# 06_-_CPU_-_HDMI_LVDS.net
KiCad netlist of a schematic drawn in Altium Designer
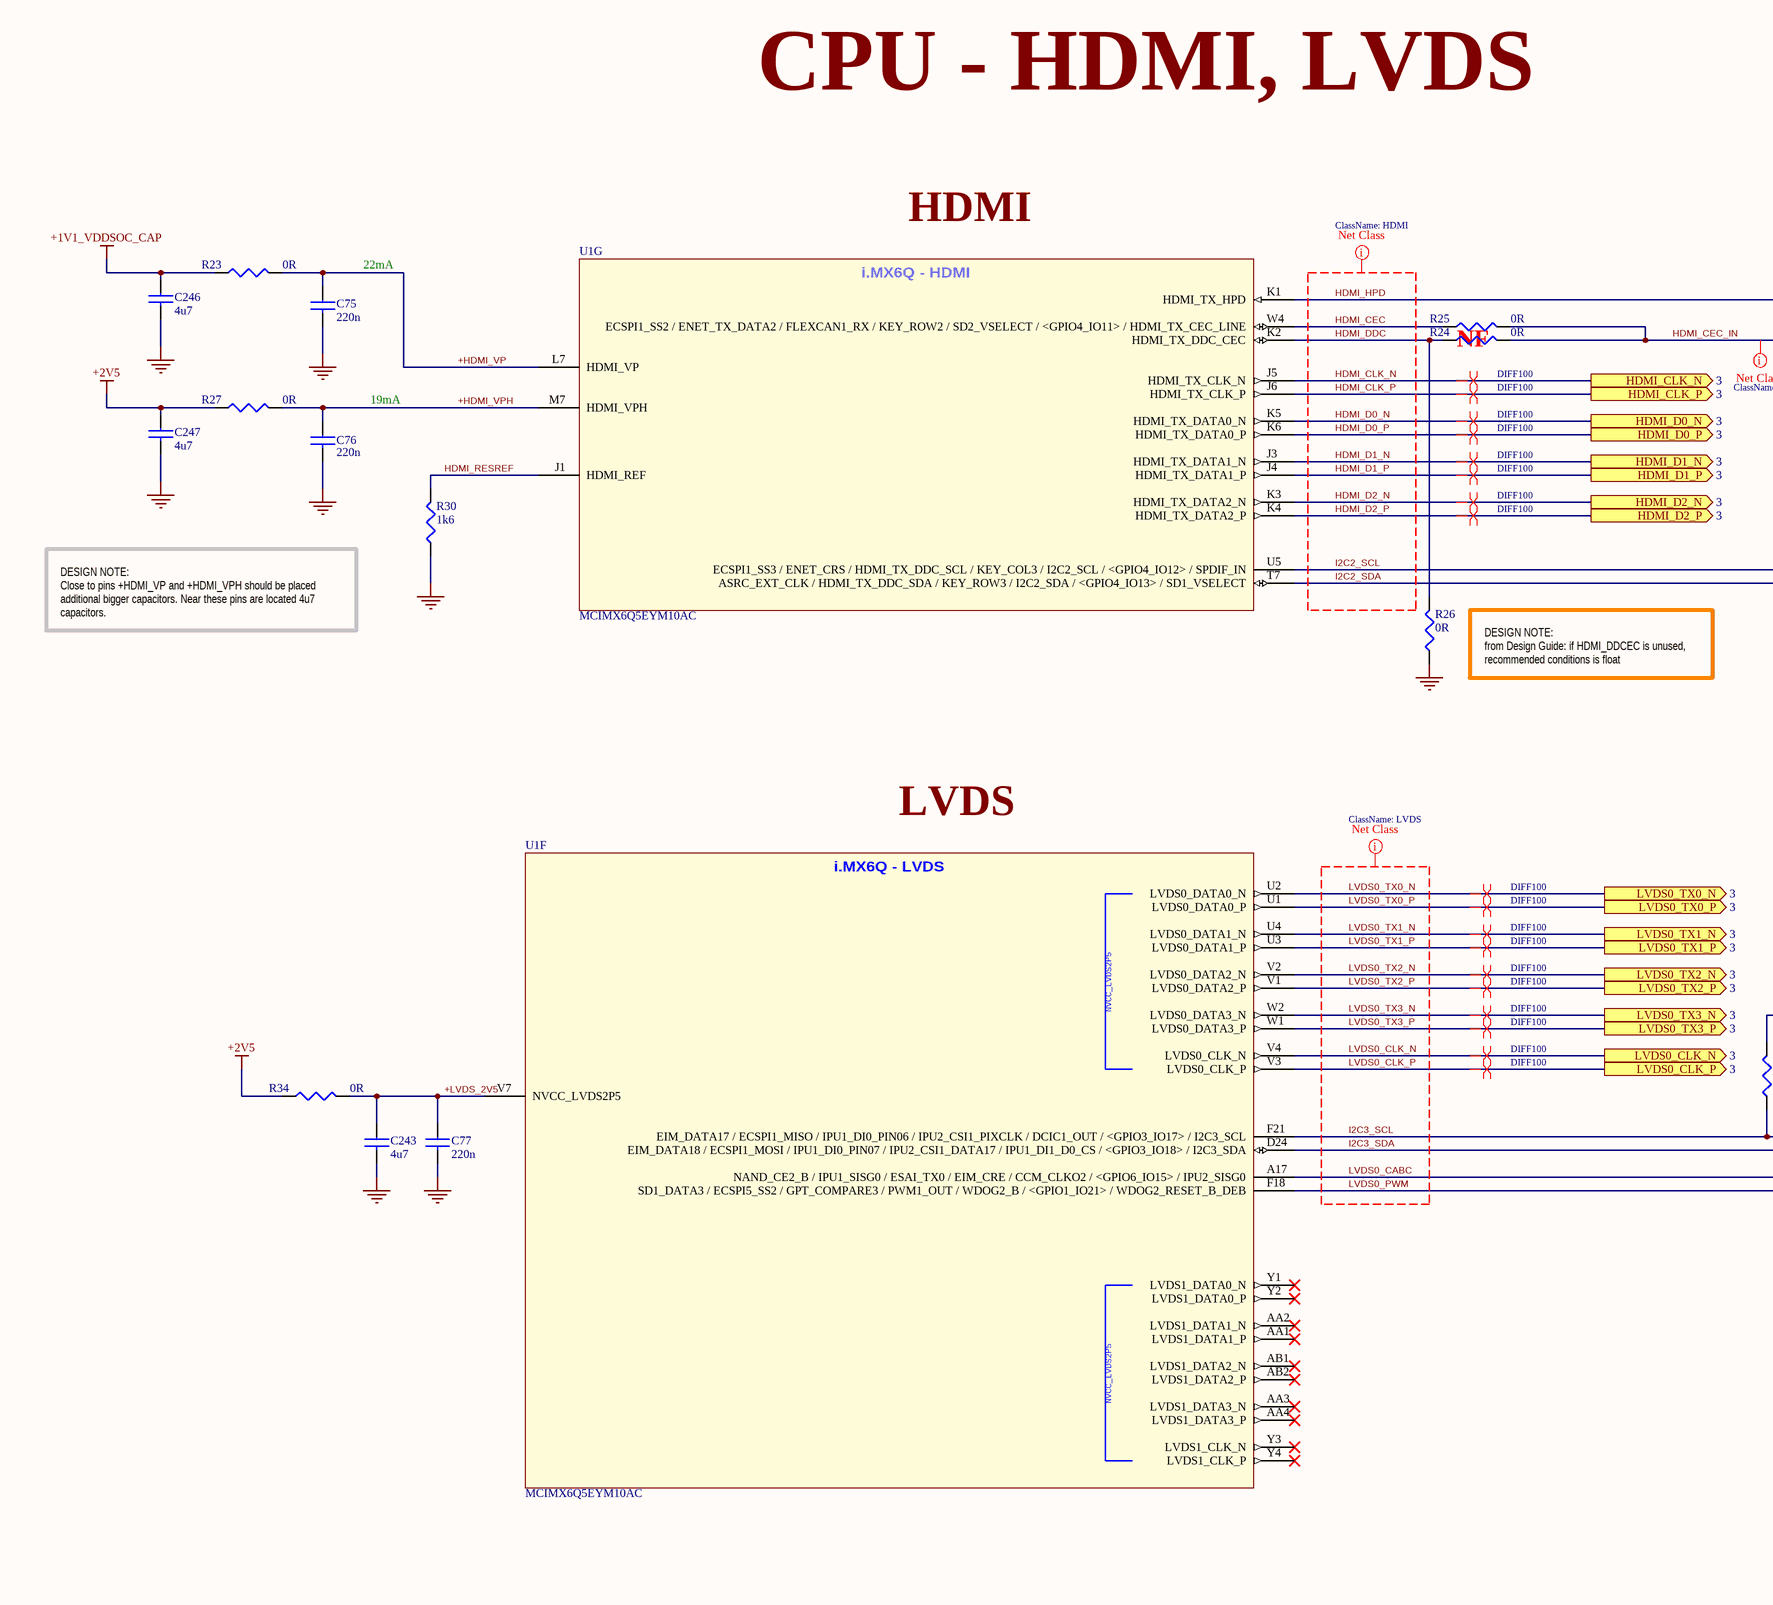
[diagram p0: [06] - CPU - HDMI, LVDS.SchDoc, left]
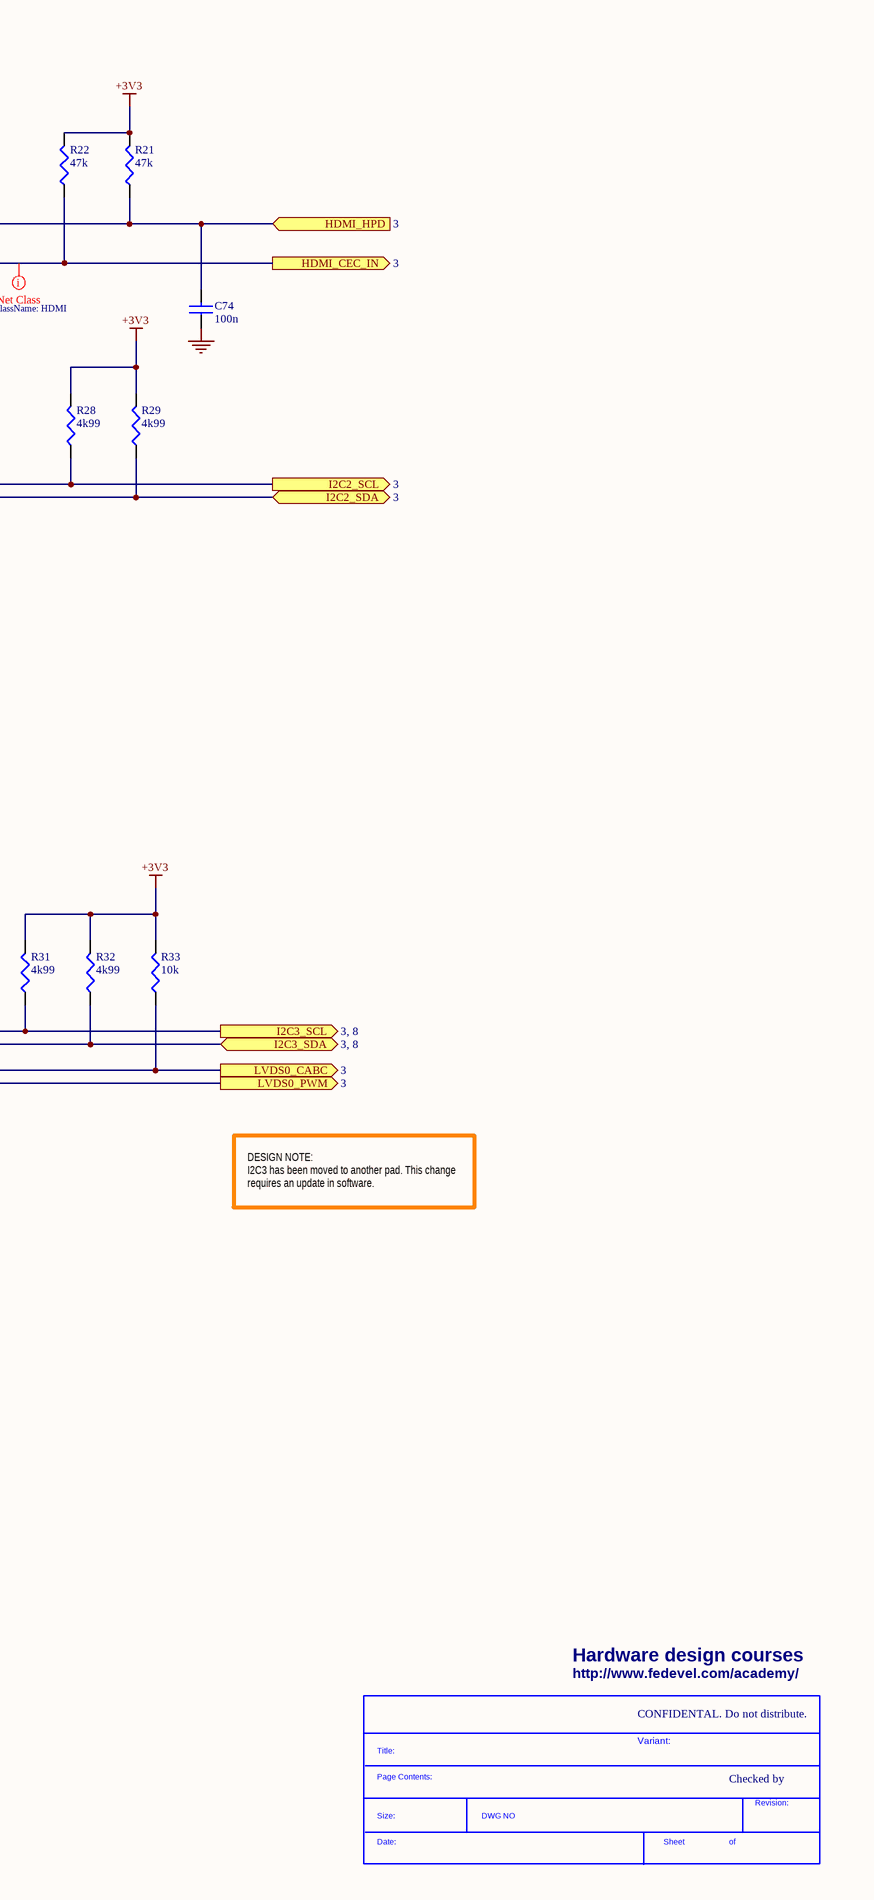
[diagram p1: [06] - CPU - HDMI, LVDS.SchDoc, right]

(export (version "E")
  (design (tool "Eeschema 10.0.6"))
  (components
    (comp (ref "C74")
      (value "100n")
      (footprint "C0402")
      (description "CAP CER .10UF 50V X5R 10% 0402")
      (fields
        (field (name "MANUFACTURER") "TDK Corporation")
        (field (name "MANUFACTURER PART NUMBER") "C1005X5R1H104K")
      )
      (libsource (lib "iMX6 Rex_V1I1") (part "C1005X5R1H104K"))
    )
    (comp (ref "C75")
      (value "220n")
      (footprint "C0402")
      (description "CAP CER .22UF 25V X5R 20% 0402")
      (fields
        (field (name "MANUFACTURER") "TDK Corporation")
        (field (name "MANUFACTURER PART NUMBER") "C1005X5R1E224M")
      )
      (libsource (lib "iMX6 Rex_V1I1") (part "C1005X5R1E224M"))
    )
    (comp (ref "C76")
      (value "220n")
      (footprint "C0402")
      (description "CAP CER .22UF 25V X5R 20% 0402")
      (fields
        (field (name "MANUFACTURER") "TDK Corporation")
        (field (name "MANUFACTURER PART NUMBER") "C1005X5R1E224M")
      )
      (libsource (lib "iMX6 Rex_V1I1") (part "C1005X5R1E224M"))
    )
    (comp (ref "C77")
      (value "220n")
      (footprint "C0402")
      (description "CAP CER .22UF 25V X5R 20% 0402")
      (fields
        (field (name "MANUFACTURER") "TDK Corporation")
        (field (name "MANUFACTURER PART NUMBER") "C1005X5R1E224M")
      )
      (libsource (lib "iMX6 Rex_V1I1") (part "C1005X5R1E224M"))
    )
    (comp (ref "C243")
      (value "4u7")
      (footprint "C0402")
      (description "CAP CER 4.7UF 10V 20% X5R 0402")
      (fields
        (field (name "MANUFACTURER") "TDK Corporation")
        (field (name "MANUFACTURER PART NUMBER") "C1005X5R1A475M")
        (field (name ".CHECKED PCB") "RF")
        (field (name ".CHECKED SCH") "RF")
      )
      (libsource (lib "iMX6 Rex_V1I1") (part "C1005X5R1A475M"))
    )
    (comp (ref "C246")
      (value "4u7")
      (footprint "C0402")
      (description "CAP CER 4.7UF 10V 20% X5R 0402")
      (fields
        (field (name "MANUFACTURER") "TDK Corporation")
        (field (name "MANUFACTURER PART NUMBER") "C1005X5R1A475M")
        (field (name ".CHECKED PCB") "RF")
        (field (name ".CHECKED SCH") "RF")
      )
      (libsource (lib "iMX6 Rex_V1I1") (part "C1005X5R1A475M"))
    )
    (comp (ref "C247")
      (value "4u7")
      (footprint "C0402")
      (description "CAP CER 4.7UF 10V 20% X5R 0402")
      (fields
        (field (name "MANUFACTURER") "TDK Corporation")
        (field (name "MANUFACTURER PART NUMBER") "C1005X5R1A475M")
        (field (name ".CHECKED PCB") "RF")
        (field (name ".CHECKED SCH") "RF")
      )
      (libsource (lib "iMX6 Rex_V1I1") (part "C1005X5R1A475M"))
    )
    (comp (ref "R21")
      (value "47k")
      (footprint "R0402")
      (description "RES 47.0K OHM 1/16W 1% 0402 SMD")
      (fields
        (field (name "MANUFACTURER") "Yageo")
        (field (name "MANUFACTURER PART NUMBER") "RC0402FR-0747KL")
      )
      (libsource (lib "iMX6 Rex_V1I1") (part "RC0402FR-0747KL"))
    )
    (comp (ref "R22")
      (value "47k")
      (footprint "R0402")
      (description "RES 47.0K OHM 1/16W 1% 0402 SMD")
      (fields
        (field (name "MANUFACTURER") "Yageo")
        (field (name "MANUFACTURER PART NUMBER") "RC0402FR-0747KL")
      )
      (libsource (lib "iMX6 Rex_V1I1") (part "RC0402FR-0747KL"))
    )
    (comp (ref "R23")
      (value "0R")
      (footprint "R0402")
      (description "RES 0.0 OHM 1/16W 0402 SMD")
      (fields
        (field (name "MANUFACTURER") "Yageo")
        (field (name "MANUFACTURER PART NUMBER") "RC0402JR-070RL")
      )
      (libsource (lib "iMX6 Rex_V1I1") (part "RC0402JR-070RL"))
    )
    (comp (ref "R24")
      (value "0R")
      (footprint "R0402")
      (description "RES 0.0 OHM 1/16W 0402 SMD")
      (fields
        (field (name "MANUFACTURER") "Yageo")
        (field (name "MANUFACTURER PART NUMBER") "RC0402JR-070RL")
      )
      (libsource (lib "iMX6 Rex_V1I1") (part "RC0402JR-070RL"))
    )
    (comp (ref "R25")
      (value "0R")
      (footprint "R0402")
      (description "RES 0.0 OHM 1/16W 0402 SMD")
      (fields
        (field (name "MANUFACTURER") "Yageo")
        (field (name "MANUFACTURER PART NUMBER") "RC0402JR-070RL")
      )
      (libsource (lib "iMX6 Rex_V1I1") (part "RC0402JR-070RL"))
    )
    (comp (ref "R26")
      (value "0R")
      (footprint "R0402")
      (description "RES 0.0 OHM 1/16W 0402 SMD")
      (fields
        (field (name "MANUFACTURER") "Yageo")
        (field (name "MANUFACTURER PART NUMBER") "RC0402JR-070RL")
      )
      (libsource (lib "iMX6 Rex_V1I1") (part "RC0402JR-070RL"))
    )
    (comp (ref "R27")
      (value "0R")
      (footprint "R0402")
      (description "RES 0.0 OHM 1/16W 0402 SMD")
      (fields
        (field (name "MANUFACTURER") "Yageo")
        (field (name "MANUFACTURER PART NUMBER") "RC0402JR-070RL")
      )
      (libsource (lib "iMX6 Rex_V1I1") (part "RC0402JR-070RL"))
    )
    (comp (ref "R28")
      (value "4k99")
      (footprint "R0402")
      (description "RES TF 4.99K OHM 1% 1/16W 0402")
      (fields
        (field (name "MANUFACTURER") "Stackpole Electronics Inc")
        (field (name "MANUFACTURER PART NUMBER") "RMCF0402FT4K99")
      )
      (libsource (lib "iMX6 Rex_V1I1") (part "RMCF0402FT4K99"))
    )
    (comp (ref "R29")
      (value "4k99")
      (footprint "R0402")
      (description "RES TF 4.99K OHM 1% 1/16W 0402")
      (fields
        (field (name "MANUFACTURER") "Stackpole Electronics Inc")
        (field (name "MANUFACTURER PART NUMBER") "RMCF0402FT4K99")
      )
      (libsource (lib "iMX6 Rex_V1I1") (part "RMCF0402FT4K99"))
    )
    (comp (ref "R30")
      (value "1k6")
      (footprint "R0402")
      (description "RES 1.6K OHM 1/10W 1% 0402 SMD")
      (fields
        (field (name "MANUFACTURER") "Panasonic Electronic Components")
        (field (name "MANUFACTURER PART NUMBER") "ERJ-2RKF1601X")
        (field (name ".CREATOR") "MM")
        (field (name ".CHECKED PCB") "RF, used by MM")
        (field (name ".CHECKED SCH") "MM, checked by RF")
      )
      (libsource (lib "iMX6 Rex_V1I1") (part "ERJ-2RKF1601X"))
    )
    (comp (ref "R31")
      (value "4k99")
      (footprint "R0402")
      (description "RES TF 4.99K OHM 1% 1/16W 0402")
      (fields
        (field (name "MANUFACTURER") "Stackpole Electronics Inc")
        (field (name "MANUFACTURER PART NUMBER") "RMCF0402FT4K99")
      )
      (libsource (lib "iMX6 Rex_V1I1") (part "RMCF0402FT4K99"))
    )
    (comp (ref "R32")
      (value "4k99")
      (footprint "R0402")
      (description "RES TF 4.99K OHM 1% 1/16W 0402")
      (fields
        (field (name "MANUFACTURER") "Stackpole Electronics Inc")
        (field (name "MANUFACTURER PART NUMBER") "RMCF0402FT4K99")
      )
      (libsource (lib "iMX6 Rex_V1I1") (part "RMCF0402FT4K99"))
    )
    (comp (ref "R33")
      (value "10k")
      (footprint "R0402")
      (description "RES 10.0K OHM 1/16W 1% 0402 SMD")
      (fields
        (field (name "MANUFACTURER") "Yageo")
        (field (name "MANUFACTURER PART NUMBER") "RC0402FR-0710KL")
      )
      (libsource (lib "iMX6 Rex_V1I1") (part "RC0402FR-0710KL"))
    )
    (comp (ref "R34")
      (value "0R")
      (footprint "R0402")
      (description "RES 0.0 OHM 1/16W 0402 SMD")
      (fields
        (field (name "MANUFACTURER") "Yageo")
        (field (name "MANUFACTURER PART NUMBER") "RC0402JR-070RL")
      )
      (libsource (lib "iMX6 Rex_V1I1") (part "RC0402JR-070RL"))
    )
    (comp (ref "U1")
      (value "MCIMX6Q5EYM10AC")
      (footprint "PBGA624")
      (description "IC MCU 32BIT ARM QUAD 624FCBGA")
      (fields
        (field (name "MANUFACTURER") "Freescale Semiconductor")
        (field (name ".CREATOR") "MM")
        (field (name ".CHECKED PCB") "MM, checked by RF")
        (field (name ".CHECKED SCH") "MM")
      )
      (libsource (lib "iMX6 Rex_V1I1") (part "MCIMX6Q5EYM10AC"))
    )
  )
  (nets
    (net (code "1") (name "+1V1_VDDSOC_CAP") (class "Default")
      (node (ref "C246") (pin "1") (pinfunction "1_1") (pintype "passive"))
      (node (ref "R23") (pin "1") (pinfunction "1_1") (pintype "passive"))
    )
    (net (code "2") (name "+2V5") (class "Default")
      (node (ref "C247") (pin "1") (pinfunction "1_1") (pintype "passive"))
      (node (ref "R27") (pin "1") (pinfunction "1_1") (pintype "passive"))
      (node (ref "R34") (pin "1") (pinfunction "1_1") (pintype "passive"))
    )
    (net (code "3") (name "+3V3") (class "Default")
      (node (ref "R21") (pin "2") (pinfunction "2_2") (pintype "passive"))
      (node (ref "R22") (pin "2") (pinfunction "2_2") (pintype "passive"))
      (node (ref "R28") (pin "2") (pinfunction "2_2") (pintype "passive"))
      (node (ref "R29") (pin "2") (pinfunction "2_2") (pintype "passive"))
      (node (ref "R31") (pin "2") (pinfunction "2_2") (pintype "passive"))
      (node (ref "R32") (pin "2") (pinfunction "2_2") (pintype "passive"))
      (node (ref "R33") (pin "2") (pinfunction "2_2") (pintype "passive"))
    )
    (net (code "4") (name "/+HDMI_VP") (class "Default")
      (node (ref "C75") (pin "1") (pinfunction "1_1") (pintype "passive"))
      (node (ref "R23") (pin "2") (pinfunction "2_2") (pintype "passive"))
      (node (ref "U1") (pin "L7") (pinfunction "HDMI_VP_L7") (pintype "power_in"))
    )
    (net (code "5") (name "/+HDMI_VPH") (class "Default")
      (node (ref "C76") (pin "1") (pinfunction "1_1") (pintype "passive"))
      (node (ref "R27") (pin "2") (pinfunction "2_2") (pintype "passive"))
      (node (ref "U1") (pin "M7") (pinfunction "HDMI_VPH_M7") (pintype "power_in"))
    )
    (net (code "6") (name "/+LVDS_2V5") (class "Default")
      (node (ref "C243") (pin "1") (pinfunction "1_1") (pintype "passive"))
      (node (ref "C77") (pin "1") (pinfunction "1_1") (pintype "passive"))
      (node (ref "R34") (pin "2") (pinfunction "2_2") (pintype "passive"))
      (node (ref "U1") (pin "V7") (pinfunction "NVCC_LVDS2P5_V7") (pintype "power_in"))
    )
    (net (code "7") (name "/HDMI_CEC") (class "Default")
      (node (ref "R25") (pin "1") (pinfunction "1_1") (pintype "passive"))
      (node (ref "U1") (pin "W4") (pinfunction "ECSPI1_SS2_/_ENET_TX_DATA2_/_FLEXCAN1_RX_/_KEY_ROW2_/_SD2_VSELECT_/_<GPIO4_IO11>_/_HDMI_TX_CEC_LINE_W4") (pintype "bidirectional"))
    )
    (net (code "8") (name "/HDMI_CEC_IN") (class "Default")
      (node (ref "R22") (pin "1") (pinfunction "1_1") (pintype "passive"))
      (node (ref "R24") (pin "2") (pinfunction "2_2") (pintype "passive"))
      (node (ref "R25") (pin "2") (pinfunction "2_2") (pintype "passive"))
    )
    (net (code "9") (name "/HDMI_CLK_N") (class "Default")
      (node (ref "U1") (pin "J5") (pinfunction "HDMI_TX_CLK_N_J5") (pintype "output"))
    )
    (net (code "10") (name "/HDMI_CLK_P") (class "Default")
      (node (ref "U1") (pin "J6") (pinfunction "HDMI_TX_CLK_P_J6") (pintype "output"))
    )
    (net (code "11") (name "/HDMI_D0_N") (class "Default")
      (node (ref "U1") (pin "K5") (pinfunction "HDMI_TX_DATA0_N_K5") (pintype "output"))
    )
    (net (code "12") (name "/HDMI_D0_P") (class "Default")
      (node (ref "U1") (pin "K6") (pinfunction "HDMI_TX_DATA0_P_K6") (pintype "output"))
    )
    (net (code "13") (name "/HDMI_D1_N") (class "Default")
      (node (ref "U1") (pin "J3") (pinfunction "HDMI_TX_DATA1_N_J3") (pintype "output"))
    )
    (net (code "14") (name "/HDMI_D1_P") (class "Default")
      (node (ref "U1") (pin "J4") (pinfunction "HDMI_TX_DATA1_P_J4") (pintype "output"))
    )
    (net (code "15") (name "/HDMI_D2_N") (class "Default")
      (node (ref "U1") (pin "K3") (pinfunction "HDMI_TX_DATA2_N_K3") (pintype "output"))
    )
    (net (code "16") (name "/HDMI_D2_P") (class "Default")
      (node (ref "U1") (pin "K4") (pinfunction "HDMI_TX_DATA2_P_K4") (pintype "output"))
    )
    (net (code "17") (name "/HDMI_DDC") (class "Default")
      (node (ref "R24") (pin "1") (pinfunction "1_1") (pintype "passive"))
      (node (ref "R26") (pin "2") (pinfunction "2_2") (pintype "passive"))
      (node (ref "U1") (pin "K2") (pinfunction "HDMI_TX_DDC_CEC_K2") (pintype "bidirectional"))
    )
    (net (code "18") (name "/HDMI_HPD") (class "Default")
      (node (ref "C74") (pin "2") (pinfunction "2_2") (pintype "passive"))
      (node (ref "R21") (pin "1") (pinfunction "1_1") (pintype "passive"))
      (node (ref "U1") (pin "K1") (pinfunction "HDMI_TX_HPD_K1") (pintype "input"))
    )
    (net (code "19") (name "/HDMI_RESREF") (class "Default")
      (node (ref "R30") (pin "2") (pinfunction "2_2") (pintype "passive"))
      (node (ref "U1") (pin "J1") (pinfunction "HDMI_REF_J1") (pintype "passive"))
    )
    (net (code "20") (name "/I2C2_SCL") (class "Default")
      (node (ref "R28") (pin "1") (pinfunction "1_1") (pintype "passive"))
      (node (ref "U1") (pin "U5") (pinfunction "ECSPI1_SS3_/_ENET_CRS_/_HDMI_TX_DDC_SCL_/_KEY_COL3_/_I2C2_SCL_/_<GPIO4_IO12>_/_SPDIF_IN_U5") (pintype "passive"))
    )
    (net (code "21") (name "/I2C2_SDA") (class "Default")
      (node (ref "R29") (pin "1") (pinfunction "1_1") (pintype "passive"))
      (node (ref "U1") (pin "T7") (pinfunction "ASRC_EXT_CLK_/_HDMI_TX_DDC_SDA_/_KEY_ROW3_/_I2C2_SDA_/_<GPIO4_IO13>_/_SD1_VSELECT_T7") (pintype "bidirectional"))
    )
    (net (code "22") (name "/I2C3_SCL") (class "Default")
      (node (ref "R31") (pin "1") (pinfunction "1_1") (pintype "passive"))
      (node (ref "U1") (pin "F21") (pinfunction "EIM_DATA17_/_ECSPI1_MISO_/_IPU1_DI0_PIN06_/_IPU2_CSI1_PIXCLK_/_DCIC1_OUT_/_<GPIO3_IO17>_/_I2C3_SCL_F21") (pintype "passive"))
    )
    (net (code "23") (name "/I2C3_SDA") (class "Default")
      (node (ref "R32") (pin "1") (pinfunction "1_1") (pintype "passive"))
      (node (ref "U1") (pin "D24") (pinfunction "EIM_DATA18_/_ECSPI1_MOSI_/_IPU1_DI0_PIN07_/_IPU2_CSI1_DATA17_/_IPU1_DI1_D0_CS_/_<GPIO3_IO18>_/_I2C3_SDA_D24") (pintype "bidirectional"))
    )
    (net (code "24") (name "/LVDS0_CABC") (class "Default")
      (node (ref "R33") (pin "1") (pinfunction "1_1") (pintype "passive"))
      (node (ref "U1") (pin "A17") (pinfunction "NAND_CE2_B_/_IPU1_SISG0_/_ESAI_TX0_/_EIM_CRE_/_CCM_CLKO2_/_<GPIO6_IO15>_/_IPU2_SISG0_A17") (pintype "passive"))
    )
    (net (code "25") (name "/LVDS0_CLK_N") (class "Default")
      (node (ref "U1") (pin "V4") (pinfunction "LVDS0_CLK_N_V4") (pintype "output"))
    )
    (net (code "26") (name "/LVDS0_CLK_P") (class "Default")
      (node (ref "U1") (pin "V3") (pinfunction "LVDS0_CLK_P_V3") (pintype "output"))
    )
    (net (code "27") (name "/LVDS0_PWM") (class "Default")
      (node (ref "U1") (pin "F18") (pinfunction "SD1_DATA3_/_ECSPI5_SS2_/_GPT_COMPARE3_/_PWM1_OUT_/_WDOG2_B_/_<GPIO1_IO21>_/_WDOG2_RESET_B_DEB_F18") (pintype "passive"))
    )
    (net (code "28") (name "/LVDS0_TX0_N") (class "Default")
      (node (ref "U1") (pin "U2") (pinfunction "LVDS0_DATA0_N_U2") (pintype "output"))
    )
    (net (code "29") (name "/LVDS0_TX0_P") (class "Default")
      (node (ref "U1") (pin "U1") (pinfunction "LVDS0_DATA0_P_U1") (pintype "output"))
    )
    (net (code "30") (name "/LVDS0_TX1_N") (class "Default")
      (node (ref "U1") (pin "U4") (pinfunction "LVDS0_DATA1_N_U4") (pintype "output"))
    )
    (net (code "31") (name "/LVDS0_TX1_P") (class "Default")
      (node (ref "U1") (pin "U3") (pinfunction "LVDS0_DATA1_P_U3") (pintype "output"))
    )
    (net (code "32") (name "/LVDS0_TX2_N") (class "Default")
      (node (ref "U1") (pin "V2") (pinfunction "LVDS0_DATA2_N_V2") (pintype "output"))
    )
    (net (code "33") (name "/LVDS0_TX2_P") (class "Default")
      (node (ref "U1") (pin "V1") (pinfunction "LVDS0_DATA2_P_V1") (pintype "output"))
    )
    (net (code "34") (name "/LVDS0_TX3_N") (class "Default")
      (node (ref "U1") (pin "W2") (pinfunction "LVDS0_DATA3_N_W2") (pintype "output"))
    )
    (net (code "35") (name "/LVDS0_TX3_P") (class "Default")
      (node (ref "U1") (pin "W1") (pinfunction "LVDS0_DATA3_P_W1") (pintype "output"))
    )
    (net (code "36") (name "GND") (class "Default")
      (node (ref "C243") (pin "2") (pinfunction "2_2") (pintype "passive"))
      (node (ref "C246") (pin "2") (pinfunction "2_2") (pintype "passive"))
      (node (ref "C247") (pin "2") (pinfunction "2_2") (pintype "passive"))
      (node (ref "C74") (pin "1") (pinfunction "1_1") (pintype "passive"))
      (node (ref "C75") (pin "2") (pinfunction "2_2") (pintype "passive"))
      (node (ref "C76") (pin "2") (pinfunction "2_2") (pintype "passive"))
      (node (ref "C77") (pin "2") (pinfunction "2_2") (pintype "passive"))
      (node (ref "R26") (pin "1") (pinfunction "1_1") (pintype "passive"))
      (node (ref "R30") (pin "1") (pinfunction "1_1") (pintype "passive"))
    )
    (net (code "37") (name "unconnected-(U1F-LVDS1_CLK_N-PadY3)") (class "Default")
      (node (ref "U1") (pin "Y3") (pinfunction "LVDS1_CLK_N_Y3") (pintype "output+no_connect"))
    )
    (net (code "38") (name "unconnected-(U1F-LVDS1_CLK_P-PadY4)") (class "Default")
      (node (ref "U1") (pin "Y4") (pinfunction "LVDS1_CLK_P_Y4") (pintype "output+no_connect"))
    )
    (net (code "39") (name "unconnected-(U1F-LVDS1_DATA0_N-PadY1)") (class "Default")
      (node (ref "U1") (pin "Y1") (pinfunction "LVDS1_DATA0_N_Y1") (pintype "output+no_connect"))
    )
    (net (code "40") (name "unconnected-(U1F-LVDS1_DATA0_P-PadY2)") (class "Default")
      (node (ref "U1") (pin "Y2") (pinfunction "LVDS1_DATA0_P_Y2") (pintype "output+no_connect"))
    )
    (net (code "41") (name "unconnected-(U1F-LVDS1_DATA1_N-PadAA2)") (class "Default")
      (node (ref "U1") (pin "AA2") (pinfunction "LVDS1_DATA1_N_AA2") (pintype "output+no_connect"))
    )
    (net (code "42") (name "unconnected-(U1F-LVDS1_DATA1_P-PadAA1)") (class "Default")
      (node (ref "U1") (pin "AA1") (pinfunction "LVDS1_DATA1_P_AA1") (pintype "output+no_connect"))
    )
    (net (code "43") (name "unconnected-(U1F-LVDS1_DATA2_N-PadAB1)") (class "Default")
      (node (ref "U1") (pin "AB1") (pinfunction "LVDS1_DATA2_N_AB1") (pintype "output+no_connect"))
    )
    (net (code "44") (name "unconnected-(U1F-LVDS1_DATA2_P-PadAB2)") (class "Default")
      (node (ref "U1") (pin "AB2") (pinfunction "LVDS1_DATA2_P_AB2") (pintype "output+no_connect"))
    )
    (net (code "45") (name "unconnected-(U1F-LVDS1_DATA3_N-PadAA3)") (class "Default")
      (node (ref "U1") (pin "AA3") (pinfunction "LVDS1_DATA3_N_AA3") (pintype "output+no_connect"))
    )
    (net (code "46") (name "unconnected-(U1F-LVDS1_DATA3_P-PadAA4)") (class "Default")
      (node (ref "U1") (pin "AA4") (pinfunction "LVDS1_DATA3_P_AA4") (pintype "output+no_connect"))
    )
  )
)
